# IMU_9K_REV_E.net
KiCad netlist of a schematic drawn in Altium Designer
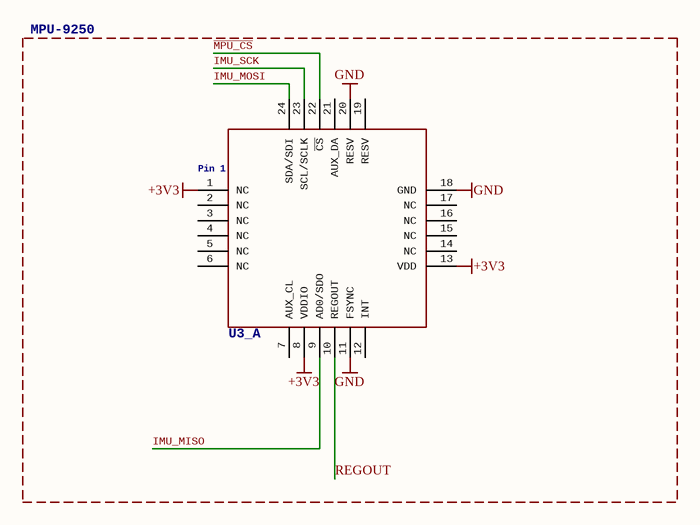
[diagram p0: IMU_9K_REV_E.SchDoc]

(export (version "E")
  (design (tool "Eeschema 10.0.6"))
  (components
    (comp (ref "U3_A")
      (value "MPU-9250")
      (footprint "MPU-9250")
      (fields (field (name "PIN 1") "Pin 1"))
      (libsource (lib "pixhawk2") (part "MPU-6500"))
    )
  )
  (nets
    (net (code "1") (name "+3V3") (class "Default")
      (node (ref "U3_A") (pin "1") (pinfunction "NC_1") (pintype "passive"))
      (node (ref "U3_A") (pin "13") (pinfunction "VDD_13") (pintype "passive"))
      (node (ref "U3_A") (pin "8") (pinfunction "VDDIO_8") (pintype "passive"))
    )
    (net (code "2") (name "/IMU_MISO") (class "Default")
      (node (ref "U3_A") (pin "9") (pinfunction "AD0/SDO_9") (pintype "passive"))
    )
    (net (code "3") (name "/IMU_MOSI") (class "Default")
      (node (ref "U3_A") (pin "24") (pinfunction "SDA/SDI_24") (pintype "passive"))
    )
    (net (code "4") (name "/IMU_SCK") (class "Default")
      (node (ref "U3_A") (pin "23") (pinfunction "SCL/SCLK_23") (pintype "passive"))
    )
    (net (code "5") (name "/REGOUT") (class "Default")
      (node (ref "U3_A") (pin "10") (pinfunction "REGOUT_10") (pintype "passive"))
    )
    (net (code "6") (name "/~{MPU_CS}") (class "Default")
      (node (ref "U3_A") (pin "22") (pinfunction "~{CS}_22") (pintype "passive"))
    )
    (net (code "7") (name "GND") (class "Default")
      (node (ref "U3_A") (pin "11") (pinfunction "FSYNC_11") (pintype "passive"))
      (node (ref "U3_A") (pin "18") (pinfunction "GND_18") (pintype "passive"))
      (node (ref "U3_A") (pin "20") (pinfunction "RESV_20") (pintype "passive"))
    )
    (net (code "8") (name "unconnected-(U3_A-AUX_CL-Pad7)") (class "Default")
      (node (ref "U3_A") (pin "7") (pinfunction "AUX_CL_7") (pintype "passive"))
    )
    (net (code "9") (name "unconnected-(U3_A-AUX_DA-Pad21)") (class "Default")
      (node (ref "U3_A") (pin "21") (pinfunction "AUX_DA_21") (pintype "passive"))
    )
    (net (code "10") (name "unconnected-(U3_A-INT-Pad12)") (class "Default")
      (node (ref "U3_A") (pin "12") (pinfunction "INT_12") (pintype "passive"))
    )
    (net (code "11") (name "unconnected-(U3_A-NC-Pad2)") (class "Default")
      (node (ref "U3_A") (pin "2") (pinfunction "NC_2") (pintype "passive"))
    )
    (net (code "12") (name "unconnected-(U3_A-NC-Pad3)") (class "Default")
      (node (ref "U3_A") (pin "3") (pinfunction "NC_3") (pintype "passive"))
    )
    (net (code "13") (name "unconnected-(U3_A-NC-Pad4)") (class "Default")
      (node (ref "U3_A") (pin "4") (pinfunction "NC_4") (pintype "passive"))
    )
    (net (code "14") (name "unconnected-(U3_A-NC-Pad5)") (class "Default")
      (node (ref "U3_A") (pin "5") (pinfunction "NC_5") (pintype "passive"))
    )
    (net (code "15") (name "unconnected-(U3_A-NC-Pad6)") (class "Default")
      (node (ref "U3_A") (pin "6") (pinfunction "NC_6") (pintype "passive"))
    )
    (net (code "16") (name "unconnected-(U3_A-NC-Pad14)") (class "Default")
      (node (ref "U3_A") (pin "14") (pinfunction "NC_14") (pintype "passive"))
    )
    (net (code "17") (name "unconnected-(U3_A-NC-Pad15)") (class "Default")
      (node (ref "U3_A") (pin "15") (pinfunction "NC_15") (pintype "passive"))
    )
    (net (code "18") (name "unconnected-(U3_A-NC-Pad16)") (class "Default")
      (node (ref "U3_A") (pin "16") (pinfunction "NC_16") (pintype "passive"))
    )
    (net (code "19") (name "unconnected-(U3_A-NC-Pad17)") (class "Default")
      (node (ref "U3_A") (pin "17") (pinfunction "NC_17") (pintype "passive"))
    )
    (net (code "20") (name "unconnected-(U3_A-RESV-Pad19)") (class "Default")
      (node (ref "U3_A") (pin "19") (pinfunction "RESV_19") (pintype "passive"))
    )
  )
)
